# mini3216_V3_0.net
KiCad netlist of a schematic drawn in Altium Designer
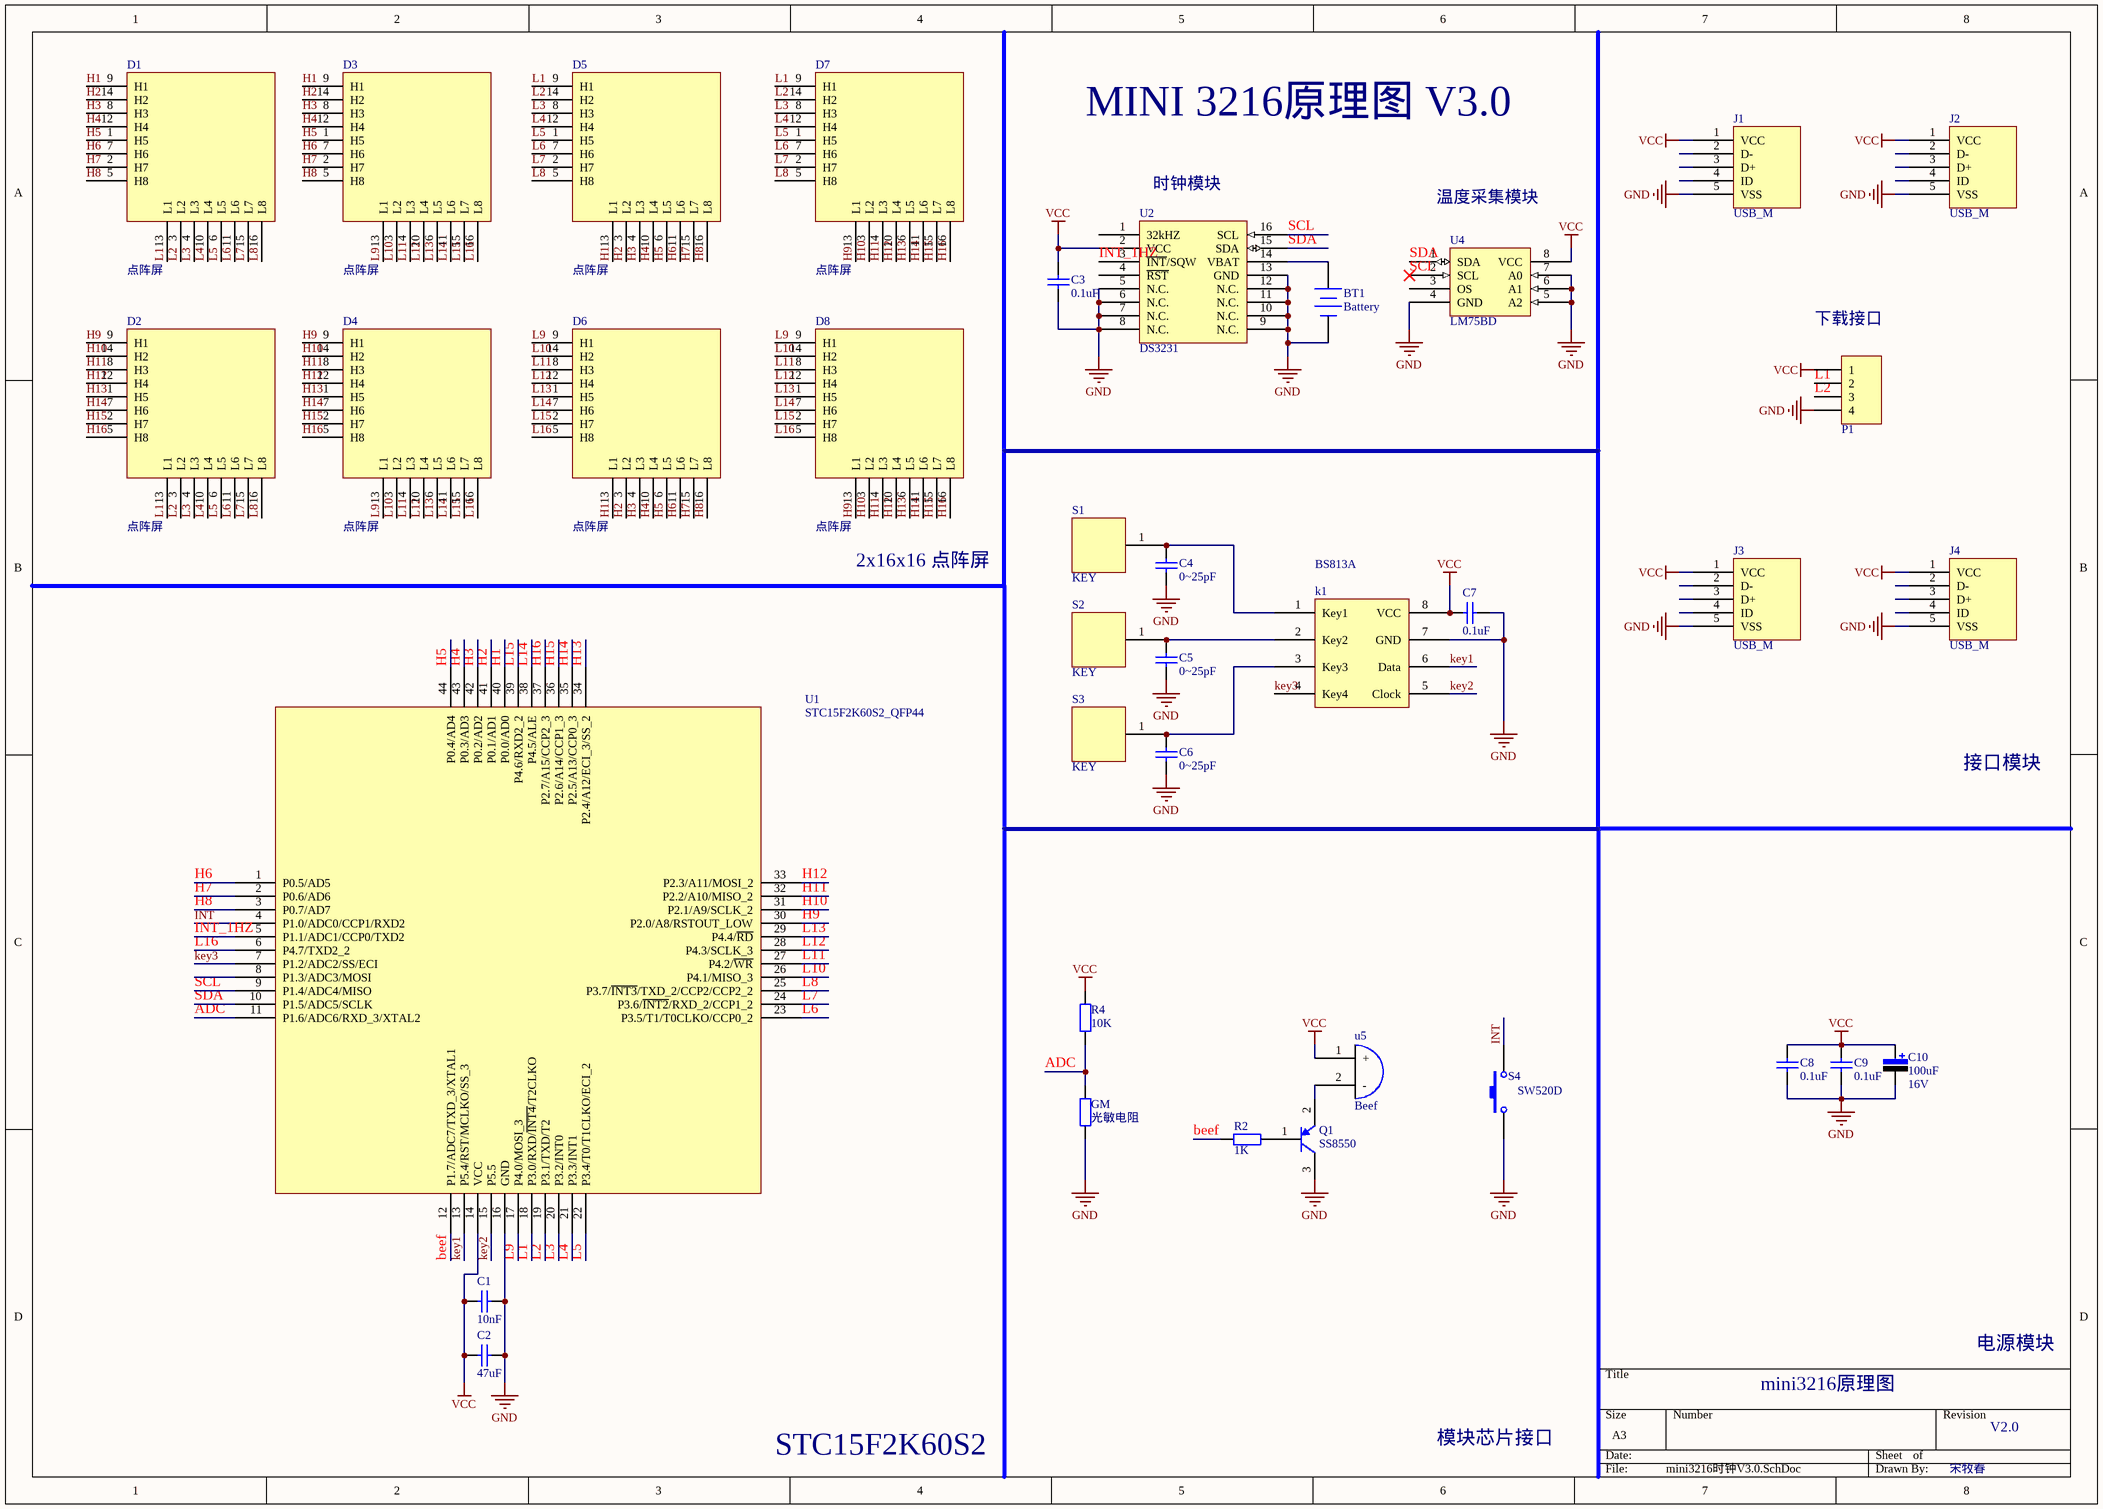
[diagram p0: mini3216时钟V3.0.SchDoc]

(export (version "E")
  (design (tool "Eeschema 10.0.6"))
  (components
    (comp (ref "BT1")
      (value "Battery")
      (footprint "CR1220电池座")
      (description "备份电池")
      (fields (field (name "PUBLISHER") "Altium Limited"))
      (libsource (lib "SMC_Devices") (part "Battery"))
    )
    (comp (ref "C1")
      (value "10nF")
      (footprint "C-RAD-0805")
      (description "无极性电容")
      (fields (field (name "Comment") "Cap") (field (name "PUBLISHER") "Altium Limited"))
      (libsource (lib "SMC_Devices") (part "Cap"))
    )
    (comp (ref "C2")
      (value "47uF")
      (footprint "1206(3216)")
      (description "无极性电容")
      (fields (field (name "Comment") "Cap") (field (name "PUBLISHER") "Altium Limited"))
      (libsource (lib "SMC_Devices") (part "Cap"))
    )
    (comp (ref "C3")
      (value "0.1uF")
      (footprint "C-RAD-0805")
      (description "无极性电容")
      (fields (field (name "Comment") "Cap") (field (name "PUBLISHER") "Altium Limited"))
      (libsource (lib "SMC_Devices") (part "Cap"))
    )
    (comp (ref "C4")
      (value "0~25pF")
      (footprint "C-RAD-0805")
      (description "无极性电容")
      (fields (field (name "Comment") "Cap") (field (name "PUBLISHER") "Altium Limited"))
      (libsource (lib "SMC_Devices") (part "Cap"))
    )
    (comp (ref "C5")
      (value "0~25pF")
      (footprint "C-RAD-0805")
      (description "无极性电容")
      (fields (field (name "Comment") "Cap") (field (name "PUBLISHER") "Altium Limited"))
      (libsource (lib "SMC_Devices") (part "Cap"))
    )
    (comp (ref "C6")
      (value "0~25pF")
      (footprint "C-RAD-0805")
      (description "无极性电容")
      (fields (field (name "Comment") "Cap") (field (name "PUBLISHER") "Altium Limited"))
      (libsource (lib "SMC_Devices") (part "Cap"))
    )
    (comp (ref "C7")
      (value "0.1uF")
      (footprint "C-RAD-0805")
      (description "无极性电容")
      (fields (field (name "Comment") "Cap") (field (name "PUBLISHER") "Altium Limited"))
      (libsource (lib "SMC_Devices") (part "Cap"))
    )
    (comp (ref "C8")
      (value "0.1uF")
      (footprint "C-RAD-0805")
      (description "无极性电容")
      (fields (field (name "Comment") "Cap") (field (name "PUBLISHER") "Altium Limited"))
      (libsource (lib "SMC_Devices") (part "Cap"))
    )
    (comp (ref "C9")
      (value "0.1uF")
      (footprint "C-RAD-0805")
      (description "无极性电容")
      (fields (field (name "Comment") "Cap") (field (name "PUBLISHER") "Altium Limited"))
      (libsource (lib "SMC_Devices") (part "Cap"))
    )
    (comp (ref "C10")
      (value "100uF")
      (footprint "CAP-3528")
      (description "极性电解电容")
      (fields
        (field (name "VOL") "16V")
        (field (name "Comment") "Cap Pol")
        (field (name "PUBLISHER") "Altium Limited")
      )
      (libsource (lib "SMC_Devices") (part "Cap Pol"))
    )
    (comp (ref "D1") (value "点阵屏") (footprint "LED_点阵1088") (libsource (lib "mini3216") (part "LED_点阵屏8x8")))
    (comp (ref "D2") (value "点阵屏") (footprint "LED_点阵1088") (libsource (lib "mini3216") (part "LED_点阵屏8x8")))
    (comp (ref "D3") (value "点阵屏") (footprint "LED_点阵1088") (libsource (lib "mini3216") (part "LED_点阵屏8x8")))
    (comp (ref "D4") (value "点阵屏") (footprint "LED_点阵1088") (libsource (lib "mini3216") (part "LED_点阵屏8x8")))
    (comp (ref "D5") (value "点阵屏") (footprint "LED_点阵1088") (libsource (lib "mini3216") (part "LED_点阵屏8x8")))
    (comp (ref "D6") (value "点阵屏") (footprint "LED_点阵1088") (libsource (lib "mini3216") (part "LED_点阵屏8x8")))
    (comp (ref "D7") (value "点阵屏") (footprint "LED_点阵1088") (libsource (lib "mini3216") (part "LED_点阵屏8x8")))
    (comp (ref "D8") (value "点阵屏") (footprint "LED_点阵1088") (libsource (lib "mini3216") (part "LED_点阵屏8x8")))
    (comp (ref "GM")
      (value "光敏电阻")
      (footprint "光敏电阻")
      (description "贴片电阻")
      (fields (field (name "Comment") "Res1") (field (name "PUBLISHER") "Altium Limited"))
      (libsource (lib "") (part "Res1_1"))
    )
    (comp (ref "J1")
      (value "USB_M")
      (footprint "USB_MICRO")
      (description "MicroUSB接口")
      (libsource (lib "SMC_Devices") (part "USB_M"))
    )
    (comp (ref "J2")
      (value "USB_M")
      (footprint "USB_MICRO")
      (description "MicroUSB接口")
      (libsource (lib "SMC_Devices") (part "USB_M"))
    )
    (comp (ref "J3")
      (value "USB_M")
      (footprint "USB_MICRO")
      (description "MicroUSB接口")
      (libsource (lib "SMC_Devices") (part "USB_M"))
    )
    (comp (ref "J4")
      (value "USB_M")
      (footprint "USB_MICRO")
      (description "MicroUSB接口")
      (libsource (lib "SMC_Devices") (part "USB_M"))
    )
    (comp (ref "k1") (value "BS813A") (footprint "SOP8") (libsource (lib "mini3216") (part "BS814A-2触摸按键")))
    (comp (ref "P1")
      (value "Header 4")
      (footprint "HDR4X1_A")
      (description "接插件")
      (fields (field (name "PUBLISHER") "Altium Limited"))
      (libsource (lib "SMC_Devices") (part "Header 4"))
    )
    (comp (ref "Q1")
      (value "SS8550")
      (footprint "SOT-23")
      (description "PNP贴片三极管")
      (fields (field (name "PUBLISHER") "Altium Limited"))
      (libsource (lib "SMC_Devices") (part "SS8550"))
    )
    (comp (ref "R2")
      (value "1K")
      (footprint "0805-1")
      (description "贴片电阻")
      (fields (field (name "Comment") "Res1") (field (name "PUBLISHER") "Altium Limited"))
      (libsource (lib "SMC_Devices") (part "Res1"))
    )
    (comp (ref "R4")
      (value "10K")
      (footprint "0805-1")
      (description "贴片电阻")
      (fields (field (name "Comment") "Res1") (field (name "PUBLISHER") "Altium Limited"))
      (libsource (lib "") (part "Res1_1"))
    )
    (comp (ref "S1") (value "KEY") (footprint "KEY1") (libsource (lib "mini3216") (part "TouchKEY")))
    (comp (ref "S2") (value "KEY") (footprint "KEY2") (libsource (lib "mini3216") (part "TouchKEY")))
    (comp (ref "S3") (value "KEY") (footprint "KEY3") (libsource (lib "mini3216") (part "TouchKEY")))
    (comp (ref "S4")
      (value "SW520D")
      (footprint "SW_PB2_A1")
      (description "微动开关")
      (fields (field (name "PUBLISHER") "Altium Limited"))
      (libsource (lib "SMC_Devices") (part "SW-PB"))
    )
    (comp (ref "U1")
      (value "STC15F2K60S2_QFP44")
      (footprint "LQFP44")
      (libsource (lib "stcmcu_altium_lib") (part "STC15F2K60S2_QFP44"))
    )
    (comp (ref "U2") (value "DS3231") (footprint "DS3231SN") (libsource (lib "mini3216") (part "DS3231")))
    (comp (ref "U4") (value "LM75BD") (footprint "LM75BD") (libsource (lib "mini3216") (part "LM75BD")))
    (comp (ref "u5") (value "Beef") (footprint "BEEF") (libsource (lib "mini3216") (part "Beef")))
  )
  (nets
    (net (code "1") (name "/ADC") (class "Default")
      (node (ref "GM") (pin "2") (pinfunction "2_2") (pintype "passive"))
      (node (ref "R4") (pin "1") (pinfunction "1_1") (pintype "passive"))
      (node (ref "U1") (pin "11") (pinfunction "P1.6/ADC6/RXD_3/XTAL2_11") (pintype "passive"))
    )
    (net (code "2") (name "/H1") (class "Default")
      (node (ref "D1") (pin "9") (pinfunction "H1_9") (pintype "passive"))
      (node (ref "D3") (pin "9") (pinfunction "H1_9") (pintype "passive"))
      (node (ref "D5") (pin "13") (pinfunction "L1_13") (pintype "passive"))
      (node (ref "D6") (pin "13") (pinfunction "L1_13") (pintype "passive"))
      (node (ref "U1") (pin "40") (pinfunction "P0.0/AD0_40") (pintype "passive"))
    )
    (net (code "3") (name "/H2") (class "Default")
      (node (ref "D1") (pin "14") (pinfunction "H2_14") (pintype "passive"))
      (node (ref "D3") (pin "14") (pinfunction "H2_14") (pintype "passive"))
      (node (ref "D5") (pin "3") (pinfunction "L2_3") (pintype "passive"))
      (node (ref "D6") (pin "3") (pinfunction "L2_3") (pintype "passive"))
      (node (ref "U1") (pin "41") (pinfunction "P0.1/AD1_41") (pintype "passive"))
    )
    (net (code "4") (name "/H3") (class "Default")
      (node (ref "D1") (pin "8") (pinfunction "H3_8") (pintype "passive"))
      (node (ref "D3") (pin "8") (pinfunction "H3_8") (pintype "passive"))
      (node (ref "D5") (pin "4") (pinfunction "L3_4") (pintype "passive"))
      (node (ref "D6") (pin "4") (pinfunction "L3_4") (pintype "passive"))
      (node (ref "U1") (pin "42") (pinfunction "P0.2/AD2_42") (pintype "passive"))
    )
    (net (code "5") (name "/H4") (class "Default")
      (node (ref "D1") (pin "12") (pinfunction "H4_12") (pintype "passive"))
      (node (ref "D3") (pin "12") (pinfunction "H4_12") (pintype "passive"))
      (node (ref "D5") (pin "10") (pinfunction "L4_10") (pintype "passive"))
      (node (ref "D6") (pin "10") (pinfunction "L4_10") (pintype "passive"))
      (node (ref "U1") (pin "43") (pinfunction "P0.3/AD3_43") (pintype "passive"))
    )
    (net (code "6") (name "/H5") (class "Default")
      (node (ref "D1") (pin "1") (pinfunction "H5_1") (pintype "passive"))
      (node (ref "D3") (pin "1") (pinfunction "H5_1") (pintype "passive"))
      (node (ref "D5") (pin "6") (pinfunction "L5_6") (pintype "passive"))
      (node (ref "D6") (pin "6") (pinfunction "L5_6") (pintype "passive"))
      (node (ref "U1") (pin "44") (pinfunction "P0.4/AD4_44") (pintype "passive"))
    )
    (net (code "7") (name "/H6") (class "Default")
      (node (ref "D1") (pin "7") (pinfunction "H6_7") (pintype "passive"))
      (node (ref "D3") (pin "7") (pinfunction "H6_7") (pintype "passive"))
      (node (ref "D5") (pin "11") (pinfunction "L6_11") (pintype "passive"))
      (node (ref "D6") (pin "11") (pinfunction "L6_11") (pintype "passive"))
      (node (ref "U1") (pin "1") (pinfunction "P0.5/AD5_1") (pintype "passive"))
    )
    (net (code "8") (name "/H7") (class "Default")
      (node (ref "D1") (pin "2") (pinfunction "H7_2") (pintype "passive"))
      (node (ref "D3") (pin "2") (pinfunction "H7_2") (pintype "passive"))
      (node (ref "D5") (pin "15") (pinfunction "L7_15") (pintype "passive"))
      (node (ref "D6") (pin "15") (pinfunction "L7_15") (pintype "passive"))
      (node (ref "U1") (pin "2") (pinfunction "P0.6/AD6_2") (pintype "passive"))
    )
    (net (code "9") (name "/H8") (class "Default")
      (node (ref "D1") (pin "5") (pinfunction "H8_5") (pintype "passive"))
      (node (ref "D3") (pin "5") (pinfunction "H8_5") (pintype "passive"))
      (node (ref "D5") (pin "16") (pinfunction "L8_16") (pintype "passive"))
      (node (ref "D6") (pin "16") (pinfunction "L8_16") (pintype "passive"))
      (node (ref "U1") (pin "3") (pinfunction "P0.7/AD7_3") (pintype "passive"))
    )
    (net (code "10") (name "/H9") (class "Default")
      (node (ref "D2") (pin "9") (pinfunction "H1_9") (pintype "passive"))
      (node (ref "D4") (pin "9") (pinfunction "H1_9") (pintype "passive"))
      (node (ref "D7") (pin "13") (pinfunction "L1_13") (pintype "passive"))
      (node (ref "D8") (pin "13") (pinfunction "L1_13") (pintype "passive"))
      (node (ref "U1") (pin "30") (pinfunction "P2.0/A8/RSTOUT_LOW_30") (pintype "passive"))
    )
    (net (code "11") (name "/H10") (class "Default")
      (node (ref "D2") (pin "14") (pinfunction "H2_14") (pintype "passive"))
      (node (ref "D4") (pin "14") (pinfunction "H2_14") (pintype "passive"))
      (node (ref "D7") (pin "3") (pinfunction "L2_3") (pintype "passive"))
      (node (ref "D8") (pin "3") (pinfunction "L2_3") (pintype "passive"))
      (node (ref "U1") (pin "31") (pinfunction "P2.1/A9/SCLK_2_31") (pintype "passive"))
    )
    (net (code "12") (name "/H11") (class "Default")
      (node (ref "D2") (pin "8") (pinfunction "H3_8") (pintype "passive"))
      (node (ref "D4") (pin "8") (pinfunction "H3_8") (pintype "passive"))
      (node (ref "D7") (pin "4") (pinfunction "L3_4") (pintype "passive"))
      (node (ref "D8") (pin "4") (pinfunction "L3_4") (pintype "passive"))
      (node (ref "U1") (pin "32") (pinfunction "P2.2/A10/MISO_2_32") (pintype "passive"))
    )
    (net (code "13") (name "/H12") (class "Default")
      (node (ref "D2") (pin "12") (pinfunction "H4_12") (pintype "passive"))
      (node (ref "D4") (pin "12") (pinfunction "H4_12") (pintype "passive"))
      (node (ref "D7") (pin "10") (pinfunction "L4_10") (pintype "passive"))
      (node (ref "D8") (pin "10") (pinfunction "L4_10") (pintype "passive"))
      (node (ref "U1") (pin "33") (pinfunction "P2.3/A11/MOSI_2_33") (pintype "passive"))
    )
    (net (code "14") (name "/H13") (class "Default")
      (node (ref "D2") (pin "1") (pinfunction "H5_1") (pintype "passive"))
      (node (ref "D4") (pin "1") (pinfunction "H5_1") (pintype "passive"))
      (node (ref "D7") (pin "6") (pinfunction "L5_6") (pintype "passive"))
      (node (ref "D8") (pin "6") (pinfunction "L5_6") (pintype "passive"))
      (node (ref "U1") (pin "34") (pinfunction "P2.4/A12/ECI_3/SS_2_34") (pintype "passive"))
    )
    (net (code "15") (name "/H14") (class "Default")
      (node (ref "D2") (pin "7") (pinfunction "H6_7") (pintype "passive"))
      (node (ref "D4") (pin "7") (pinfunction "H6_7") (pintype "passive"))
      (node (ref "D7") (pin "11") (pinfunction "L6_11") (pintype "passive"))
      (node (ref "D8") (pin "11") (pinfunction "L6_11") (pintype "passive"))
      (node (ref "U1") (pin "35") (pinfunction "P2.5/A13/CCP0_3_35") (pintype "passive"))
    )
    (net (code "16") (name "/H15") (class "Default")
      (node (ref "D2") (pin "2") (pinfunction "H7_2") (pintype "passive"))
      (node (ref "D4") (pin "2") (pinfunction "H7_2") (pintype "passive"))
      (node (ref "D7") (pin "15") (pinfunction "L7_15") (pintype "passive"))
      (node (ref "D8") (pin "15") (pinfunction "L7_15") (pintype "passive"))
      (node (ref "U1") (pin "36") (pinfunction "P2.6/A14/CCP1_3_36") (pintype "passive"))
    )
    (net (code "17") (name "/H16") (class "Default")
      (node (ref "D2") (pin "5") (pinfunction "H8_5") (pintype "passive"))
      (node (ref "D4") (pin "5") (pinfunction "H8_5") (pintype "passive"))
      (node (ref "D7") (pin "16") (pinfunction "L8_16") (pintype "passive"))
      (node (ref "D8") (pin "16") (pinfunction "L8_16") (pintype "passive"))
      (node (ref "U1") (pin "37") (pinfunction "P2.7/A15/CCP2_3_37") (pintype "passive"))
    )
    (net (code "18") (name "/INT") (class "Default")
      (node (ref "S4") (pin "2") (pinfunction "2_2") (pintype "passive"))
      (node (ref "U1") (pin "4") (pinfunction "P1.0/ADC0/CCP1/RXD2_4") (pintype "passive"))
    )
    (net (code "19") (name "/INT_1HZ") (class "Default")
      (node (ref "U1") (pin "5") (pinfunction "P1.1/ADC1/CCP0/TXD2_5") (pintype "passive"))
      (node (ref "U2") (pin "3") (pinfunction "~{INT}/SQW_3") (pintype "open_collector"))
    )
    (net (code "20") (name "/L1") (class "Default")
      (node (ref "D1") (pin "13") (pinfunction "L1_13") (pintype "passive"))
      (node (ref "D2") (pin "13") (pinfunction "L1_13") (pintype "passive"))
      (node (ref "D5") (pin "9") (pinfunction "H1_9") (pintype "passive"))
      (node (ref "D7") (pin "9") (pinfunction "H1_9") (pintype "passive"))
      (node (ref "P1") (pin "2") (pinfunction "2_2") (pintype "passive"))
      (node (ref "U1") (pin "18") (pinfunction "P3.0/RXD/~{INT4}/T2CLKO_18") (pintype "passive"))
    )
    (net (code "21") (name "/L2") (class "Default")
      (node (ref "D1") (pin "3") (pinfunction "L2_3") (pintype "passive"))
      (node (ref "D2") (pin "3") (pinfunction "L2_3") (pintype "passive"))
      (node (ref "D5") (pin "14") (pinfunction "H2_14") (pintype "passive"))
      (node (ref "D7") (pin "14") (pinfunction "H2_14") (pintype "passive"))
      (node (ref "P1") (pin "3") (pinfunction "3_3") (pintype "passive"))
      (node (ref "U1") (pin "19") (pinfunction "P3.1/TXD/T2_19") (pintype "passive"))
    )
    (net (code "22") (name "/L3") (class "Default")
      (node (ref "D1") (pin "4") (pinfunction "L3_4") (pintype "passive"))
      (node (ref "D2") (pin "4") (pinfunction "L3_4") (pintype "passive"))
      (node (ref "D5") (pin "8") (pinfunction "H3_8") (pintype "passive"))
      (node (ref "D7") (pin "8") (pinfunction "H3_8") (pintype "passive"))
      (node (ref "U1") (pin "20") (pinfunction "P3.2/INT0_20") (pintype "passive"))
    )
    (net (code "23") (name "/L4") (class "Default")
      (node (ref "D1") (pin "10") (pinfunction "L4_10") (pintype "passive"))
      (node (ref "D2") (pin "10") (pinfunction "L4_10") (pintype "passive"))
      (node (ref "D5") (pin "12") (pinfunction "H4_12") (pintype "passive"))
      (node (ref "D7") (pin "12") (pinfunction "H4_12") (pintype "passive"))
      (node (ref "U1") (pin "21") (pinfunction "P3.3/INT1_21") (pintype "passive"))
    )
    (net (code "24") (name "/L5") (class "Default")
      (node (ref "D1") (pin "6") (pinfunction "L5_6") (pintype "passive"))
      (node (ref "D2") (pin "6") (pinfunction "L5_6") (pintype "passive"))
      (node (ref "D5") (pin "1") (pinfunction "H5_1") (pintype "passive"))
      (node (ref "D7") (pin "1") (pinfunction "H5_1") (pintype "passive"))
      (node (ref "U1") (pin "22") (pinfunction "P3.4/T0/T1CLKO/ECI_2_22") (pintype "passive"))
    )
    (net (code "25") (name "/L6") (class "Default")
      (node (ref "D1") (pin "11") (pinfunction "L6_11") (pintype "passive"))
      (node (ref "D2") (pin "11") (pinfunction "L6_11") (pintype "passive"))
      (node (ref "D5") (pin "7") (pinfunction "H6_7") (pintype "passive"))
      (node (ref "D7") (pin "7") (pinfunction "H6_7") (pintype "passive"))
      (node (ref "U1") (pin "23") (pinfunction "P3.5/T1/T0CLKO/CCP0_2_23") (pintype "passive"))
    )
    (net (code "26") (name "/L7") (class "Default")
      (node (ref "D1") (pin "15") (pinfunction "L7_15") (pintype "passive"))
      (node (ref "D2") (pin "15") (pinfunction "L7_15") (pintype "passive"))
      (node (ref "D5") (pin "2") (pinfunction "H7_2") (pintype "passive"))
      (node (ref "D7") (pin "2") (pinfunction "H7_2") (pintype "passive"))
      (node (ref "U1") (pin "24") (pinfunction "P3.6/~{INT2}/RXD_2/CCP1_2_24") (pintype "passive"))
    )
    (net (code "27") (name "/L8") (class "Default")
      (node (ref "D1") (pin "16") (pinfunction "L8_16") (pintype "passive"))
      (node (ref "D2") (pin "16") (pinfunction "L8_16") (pintype "passive"))
      (node (ref "D5") (pin "5") (pinfunction "H8_5") (pintype "passive"))
      (node (ref "D7") (pin "5") (pinfunction "H8_5") (pintype "passive"))
      (node (ref "U1") (pin "25") (pinfunction "P3.7/~{INT3}/TXD_2/CCP2/CCP2_2_25") (pintype "passive"))
    )
    (net (code "28") (name "/L9") (class "Default")
      (node (ref "D3") (pin "13") (pinfunction "L1_13") (pintype "passive"))
      (node (ref "D4") (pin "13") (pinfunction "L1_13") (pintype "passive"))
      (node (ref "D6") (pin "9") (pinfunction "H1_9") (pintype "passive"))
      (node (ref "D8") (pin "9") (pinfunction "H1_9") (pintype "passive"))
      (node (ref "U1") (pin "17") (pinfunction "P4.0/MOSI_3_17") (pintype "passive"))
    )
    (net (code "29") (name "/L10") (class "Default")
      (node (ref "D3") (pin "3") (pinfunction "L2_3") (pintype "passive"))
      (node (ref "D4") (pin "3") (pinfunction "L2_3") (pintype "passive"))
      (node (ref "D6") (pin "14") (pinfunction "H2_14") (pintype "passive"))
      (node (ref "D8") (pin "14") (pinfunction "H2_14") (pintype "passive"))
      (node (ref "U1") (pin "26") (pinfunction "P4.1/MISO_3_26") (pintype "passive"))
    )
    (net (code "30") (name "/L11") (class "Default")
      (node (ref "D3") (pin "4") (pinfunction "L3_4") (pintype "passive"))
      (node (ref "D4") (pin "4") (pinfunction "L3_4") (pintype "passive"))
      (node (ref "D6") (pin "8") (pinfunction "H3_8") (pintype "passive"))
      (node (ref "D8") (pin "8") (pinfunction "H3_8") (pintype "passive"))
      (node (ref "U1") (pin "27") (pinfunction "P4.2/~{WR}_27") (pintype "passive"))
    )
    (net (code "31") (name "/L12") (class "Default")
      (node (ref "D3") (pin "10") (pinfunction "L4_10") (pintype "passive"))
      (node (ref "D4") (pin "10") (pinfunction "L4_10") (pintype "passive"))
      (node (ref "D6") (pin "12") (pinfunction "H4_12") (pintype "passive"))
      (node (ref "D8") (pin "12") (pinfunction "H4_12") (pintype "passive"))
      (node (ref "U1") (pin "28") (pinfunction "P4.3/SCLK_3_28") (pintype "passive"))
    )
    (net (code "32") (name "/L13") (class "Default")
      (node (ref "D3") (pin "6") (pinfunction "L5_6") (pintype "passive"))
      (node (ref "D4") (pin "6") (pinfunction "L5_6") (pintype "passive"))
      (node (ref "D6") (pin "1") (pinfunction "H5_1") (pintype "passive"))
      (node (ref "D8") (pin "1") (pinfunction "H5_1") (pintype "passive"))
      (node (ref "U1") (pin "29") (pinfunction "P4.4/~{RD}_29") (pintype "passive"))
    )
    (net (code "33") (name "/L14") (class "Default")
      (node (ref "D3") (pin "11") (pinfunction "L6_11") (pintype "passive"))
      (node (ref "D4") (pin "11") (pinfunction "L6_11") (pintype "passive"))
      (node (ref "D6") (pin "7") (pinfunction "H6_7") (pintype "passive"))
      (node (ref "D8") (pin "7") (pinfunction "H6_7") (pintype "passive"))
      (node (ref "U1") (pin "38") (pinfunction "P4.5/ALE_38") (pintype "passive"))
    )
    (net (code "34") (name "/L15") (class "Default")
      (node (ref "D3") (pin "15") (pinfunction "L7_15") (pintype "passive"))
      (node (ref "D4") (pin "15") (pinfunction "L7_15") (pintype "passive"))
      (node (ref "D6") (pin "2") (pinfunction "H7_2") (pintype "passive"))
      (node (ref "D8") (pin "2") (pinfunction "H7_2") (pintype "passive"))
      (node (ref "U1") (pin "39") (pinfunction "P4.6/RXD2_2_39") (pintype "passive"))
    )
    (net (code "35") (name "/L16") (class "Default")
      (node (ref "D3") (pin "16") (pinfunction "L8_16") (pintype "passive"))
      (node (ref "D4") (pin "16") (pinfunction "L8_16") (pintype "passive"))
      (node (ref "D6") (pin "5") (pinfunction "H8_5") (pintype "passive"))
      (node (ref "D8") (pin "5") (pinfunction "H8_5") (pintype "passive"))
      (node (ref "U1") (pin "6") (pinfunction "P4.7/TXD2_2_6") (pintype "passive"))
    )
    (net (code "36") (name "/SCL") (class "Default")
      (node (ref "U1") (pin "9") (pinfunction "P1.4/ADC4/MISO_9") (pintype "passive"))
      (node (ref "U2") (pin "16") (pinfunction "SCL_16") (pintype "input"))
      (node (ref "U4") (pin "2") (pinfunction "SCL_2") (pintype "input"))
    )
    (net (code "37") (name "/SDA") (class "Default")
      (node (ref "U1") (pin "10") (pinfunction "P1.5/ADC5/SCLK_10") (pintype "passive"))
      (node (ref "U2") (pin "15") (pinfunction "SDA_15") (pintype "bidirectional"))
      (node (ref "U4") (pin "1") (pinfunction "SDA_1") (pintype "bidirectional"))
    )
    (net (code "38") (name "/beef") (class "Default")
      (node (ref "R2") (pin "1") (pinfunction "1_1") (pintype "passive"))
      (node (ref "U1") (pin "12") (pinfunction "P1.7/ADC7/TXD_3/XTAL1_12") (pintype "passive"))
    )
    (net (code "39") (name "/key1") (class "Default")
      (node (ref "U1") (pin "13") (pinfunction "P5.4/RST/MCLKO/SS_3_13") (pintype "passive"))
      (node (ref "k1") (pin "6") (pinfunction "Data_6") (pintype "passive"))
    )
    (net (code "40") (name "/key2") (class "Default")
      (node (ref "U1") (pin "15") (pinfunction "P5.5_15") (pintype "passive"))
      (node (ref "k1") (pin "5") (pinfunction "Clock_5") (pintype "passive"))
    )
    (net (code "41") (name "/key3") (class "Default")
      (node (ref "U1") (pin "7") (pinfunction "P1.2/ADC2/SS/ECI_7") (pintype "passive"))
      (node (ref "k1") (pin "4") (pinfunction "Key4_4") (pintype "passive"))
    )
    (net (code "42") (name "GND") (class "Default")
      (node (ref "BT1") (pin "2") (pinfunction "-_2") (pintype "passive"))
      (node (ref "C1") (pin "2") (pinfunction "2_2") (pintype "passive"))
      (node (ref "C10") (pin "2") (pinfunction "2_2") (pintype "passive"))
      (node (ref "C2") (pin "2") (pinfunction "2_2") (pintype "passive"))
      (node (ref "C3") (pin "1") (pinfunction "1_1") (pintype "passive"))
      (node (ref "C4") (pin "1") (pinfunction "1_1") (pintype "passive"))
      (node (ref "C5") (pin "1") (pinfunction "1_1") (pintype "passive"))
      (node (ref "C6") (pin "1") (pinfunction "1_1") (pintype "passive"))
      (node (ref "C7") (pin "2") (pinfunction "2_2") (pintype "passive"))
      (node (ref "C8") (pin "1") (pinfunction "1_1") (pintype "passive"))
      (node (ref "C9") (pin "1") (pinfunction "1_1") (pintype "passive"))
      (node (ref "GM") (pin "1") (pinfunction "1_1") (pintype "passive"))
      (node (ref "J1") (pin "5") (pinfunction "VSS_5") (pintype "passive"))
      (node (ref "J2") (pin "5") (pinfunction "VSS_5") (pintype "passive"))
      (node (ref "J3") (pin "5") (pinfunction "VSS_5") (pintype "passive"))
      (node (ref "J4") (pin "5") (pinfunction "VSS_5") (pintype "passive"))
      (node (ref "P1") (pin "4") (pinfunction "4_4") (pintype "passive"))
      (node (ref "Q1") (pin "3") (pinfunction "C_3") (pintype "passive"))
      (node (ref "S4") (pin "1") (pinfunction "1_1") (pintype "passive"))
      (node (ref "U1") (pin "16") (pinfunction "GND_16") (pintype "passive"))
      (node (ref "U2") (pin "10") (pinfunction "N.C._10") (pintype "passive"))
      (node (ref "U2") (pin "11") (pinfunction "N.C._11") (pintype "passive"))
      (node (ref "U2") (pin "12") (pinfunction "N.C._12") (pintype "passive"))
      (node (ref "U2") (pin "13") (pinfunction "GND_13") (pintype "power_in"))
      (node (ref "U2") (pin "5") (pinfunction "N.C._5") (pintype "passive"))
      (node (ref "U2") (pin "6") (pinfunction "N.C._6") (pintype "passive"))
      (node (ref "U2") (pin "7") (pinfunction "N.C._7") (pintype "passive"))
      (node (ref "U2") (pin "8") (pinfunction "N.C._8") (pintype "passive"))
      (node (ref "U2") (pin "9") (pinfunction "N.C._9") (pintype "passive"))
      (node (ref "U4") (pin "4") (pinfunction "GND_4") (pintype "power_in"))
      (node (ref "U4") (pin "5") (pinfunction "A2_5") (pintype "input"))
      (node (ref "U4") (pin "6") (pinfunction "A1_6") (pintype "input"))
      (node (ref "U4") (pin "7") (pinfunction "A0_7") (pintype "input"))
      (node (ref "k1") (pin "7") (pinfunction "GND_7") (pintype "passive"))
    )
    (net (code "43") (name "Net-(BT1-+)") (class "Default")
      (node (ref "BT1") (pin "1") (pinfunction "+_1") (pintype "passive"))
      (node (ref "U2") (pin "14") (pinfunction "VBAT_14") (pintype "power_in"))
    )
    (net (code "44") (name "Net-(Q1-B)") (class "Default")
      (node (ref "Q1") (pin "1") (pinfunction "B_1") (pintype "passive"))
      (node (ref "R2") (pin "2") (pinfunction "2_2") (pintype "passive"))
    )
    (net (code "45") (name "Net-(Q1-E)") (class "Default")
      (node (ref "Q1") (pin "2") (pinfunction "E_2") (pintype "passive"))
      (node (ref "u5") (pin "2") (pinfunction "-_2") (pintype "passive"))
    )
    (net (code "46") (name "Net-(k1-Key1)") (class "Default")
      (node (ref "C4") (pin "2") (pinfunction "2_2") (pintype "passive"))
      (node (ref "S1") (pin "1") (pinfunction "1_1") (pintype "passive"))
      (node (ref "k1") (pin "1") (pinfunction "Key1_1") (pintype "passive"))
    )
    (net (code "47") (name "Net-(k1-Key2)") (class "Default")
      (node (ref "C5") (pin "2") (pinfunction "2_2") (pintype "passive"))
      (node (ref "S2") (pin "1") (pinfunction "1_1") (pintype "passive"))
      (node (ref "k1") (pin "2") (pinfunction "Key2_2") (pintype "passive"))
    )
    (net (code "48") (name "Net-(k1-Key3)") (class "Default")
      (node (ref "C6") (pin "2") (pinfunction "2_2") (pintype "passive"))
      (node (ref "S3") (pin "1") (pinfunction "1_1") (pintype "passive"))
      (node (ref "k1") (pin "3") (pinfunction "Key3_3") (pintype "passive"))
    )
    (net (code "49") (name "VCC") (class "Default")
      (node (ref "C1") (pin "1") (pinfunction "1_1") (pintype "passive"))
      (node (ref "C10") (pin "1") (pinfunction "1_1") (pintype "passive"))
      (node (ref "C2") (pin "1") (pinfunction "1_1") (pintype "passive"))
      (node (ref "C3") (pin "2") (pinfunction "2_2") (pintype "passive"))
      (node (ref "C7") (pin "1") (pinfunction "1_1") (pintype "passive"))
      (node (ref "C8") (pin "2") (pinfunction "2_2") (pintype "passive"))
      (node (ref "C9") (pin "2") (pinfunction "2_2") (pintype "passive"))
      (node (ref "J1") (pin "1") (pinfunction "VCC_1") (pintype "passive"))
      (node (ref "J2") (pin "1") (pinfunction "VCC_1") (pintype "passive"))
      (node (ref "J3") (pin "1") (pinfunction "VCC_1") (pintype "passive"))
      (node (ref "J4") (pin "1") (pinfunction "VCC_1") (pintype "passive"))
      (node (ref "P1") (pin "1") (pinfunction "1_1") (pintype "passive"))
      (node (ref "R4") (pin "2") (pinfunction "2_2") (pintype "passive"))
      (node (ref "U1") (pin "14") (pinfunction "VCC_14") (pintype "passive"))
      (node (ref "U2") (pin "2") (pinfunction "VCC_2") (pintype "power_in"))
      (node (ref "U4") (pin "8") (pinfunction "VCC_8") (pintype "power_in"))
      (node (ref "k1") (pin "8") (pinfunction "VCC_8") (pintype "passive"))
      (node (ref "u5") (pin "1") (pinfunction "+_1") (pintype "power_in"))
    )
    (net (code "50") (name "unconnected-(J1-D+-Pad3)") (class "Default")
      (node (ref "J1") (pin "3") (pinfunction "D+_3") (pintype "passive"))
    )
    (net (code "51") (name "unconnected-(J1-D--Pad2)") (class "Default")
      (node (ref "J1") (pin "2") (pinfunction "D-_2") (pintype "passive"))
    )
    (net (code "52") (name "unconnected-(J1-ID-Pad4)") (class "Default")
      (node (ref "J1") (pin "4") (pinfunction "ID_4") (pintype "passive"))
    )
    (net (code "53") (name "unconnected-(J2-D+-Pad3)") (class "Default")
      (node (ref "J2") (pin "3") (pinfunction "D+_3") (pintype "passive"))
    )
    (net (code "54") (name "unconnected-(J2-D--Pad2)") (class "Default")
      (node (ref "J2") (pin "2") (pinfunction "D-_2") (pintype "passive"))
    )
    (net (code "55") (name "unconnected-(J2-ID-Pad4)") (class "Default")
      (node (ref "J2") (pin "4") (pinfunction "ID_4") (pintype "passive"))
    )
    (net (code "56") (name "unconnected-(J3-D+-Pad3)") (class "Default")
      (node (ref "J3") (pin "3") (pinfunction "D+_3") (pintype "passive"))
    )
    (net (code "57") (name "unconnected-(J3-D--Pad2)") (class "Default")
      (node (ref "J3") (pin "2") (pinfunction "D-_2") (pintype "passive"))
    )
    (net (code "58") (name "unconnected-(J3-ID-Pad4)") (class "Default")
      (node (ref "J3") (pin "4") (pinfunction "ID_4") (pintype "passive"))
    )
    (net (code "59") (name "unconnected-(J4-D+-Pad3)") (class "Default")
      (node (ref "J4") (pin "3") (pinfunction "D+_3") (pintype "passive"))
    )
    (net (code "60") (name "unconnected-(J4-D--Pad2)") (class "Default")
      (node (ref "J4") (pin "2") (pinfunction "D-_2") (pintype "passive"))
    )
    (net (code "61") (name "unconnected-(J4-ID-Pad4)") (class "Default")
      (node (ref "J4") (pin "4") (pinfunction "ID_4") (pintype "passive"))
    )
    (net (code "62") (name "unconnected-(U1-P1.3{slash}ADC3{slash}MOSI-Pad8)") (class "Default")
      (node (ref "U1") (pin "8") (pinfunction "P1.3/ADC3/MOSI_8") (pintype "passive"))
    )
    (net (code "63") (name "unconnected-(U2-32kHZ-Pad1)") (class "Default")
      (node (ref "U2") (pin "1") (pinfunction "32kHZ_1") (pintype "open_collector"))
    )
    (net (code "64") (name "unconnected-(U2-~{RST}-Pad4)") (class "Default")
      (node (ref "U2") (pin "4") (pinfunction "~{RST}_4") (pintype "open_collector"))
    )
    (net (code "65") (name "unconnected-(U4-OS-Pad3)") (class "Default")
      (node (ref "U4") (pin "3") (pinfunction "OS_3") (pintype "open_collector"))
    )
  )
)
